# Cosmic_Pi_Main_Board_V2_4_OHWR.net
KiCad netlist of a schematic drawn in EAGLE
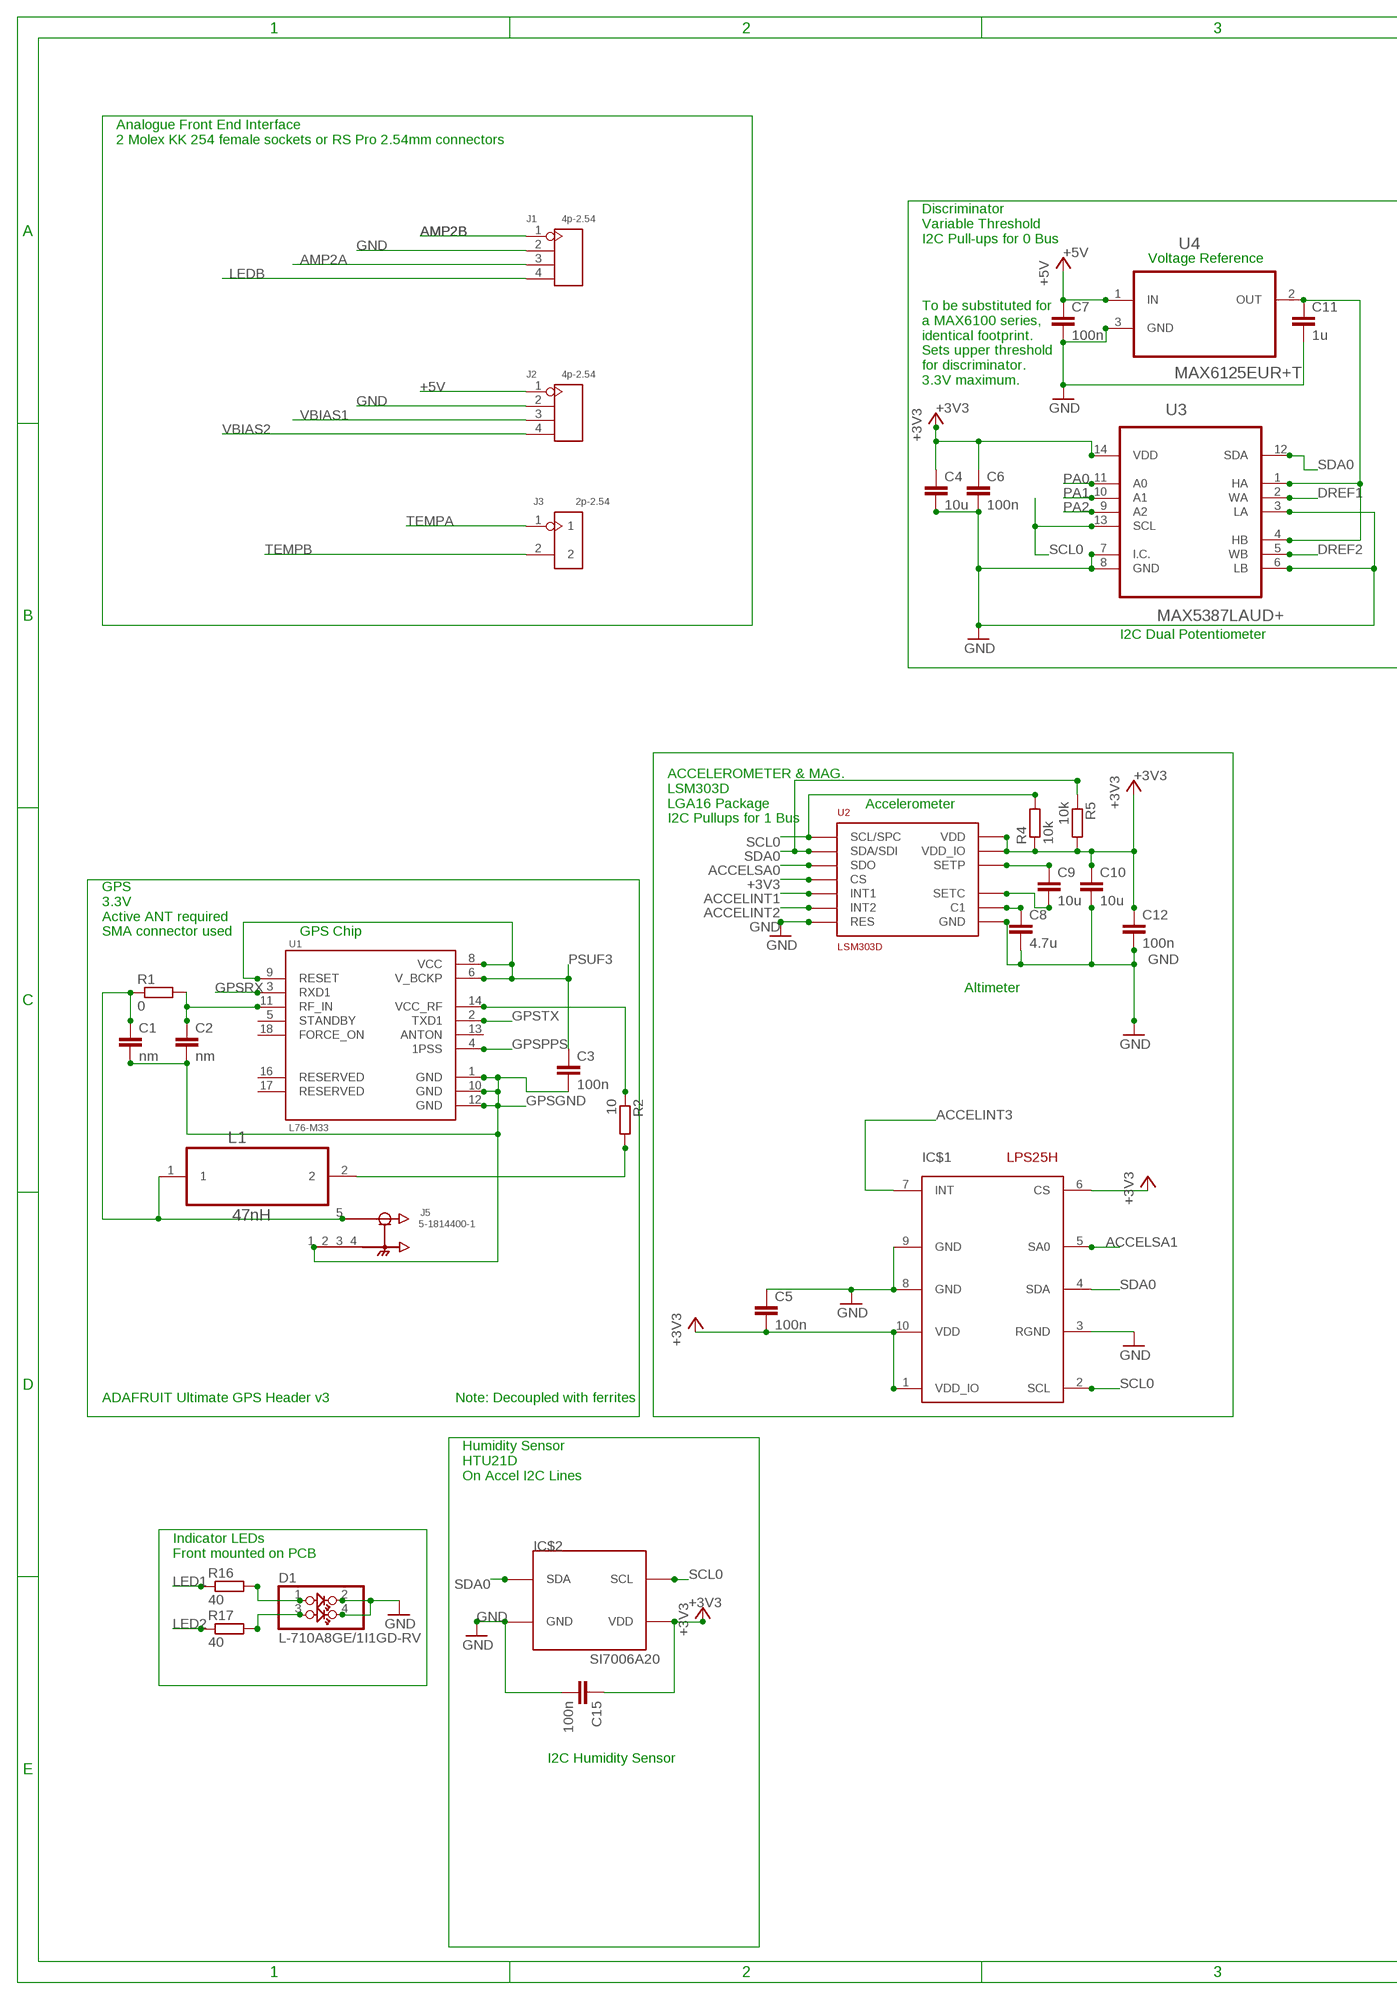
[diagram p0: schematic, sheet 1, part 1 of 2]
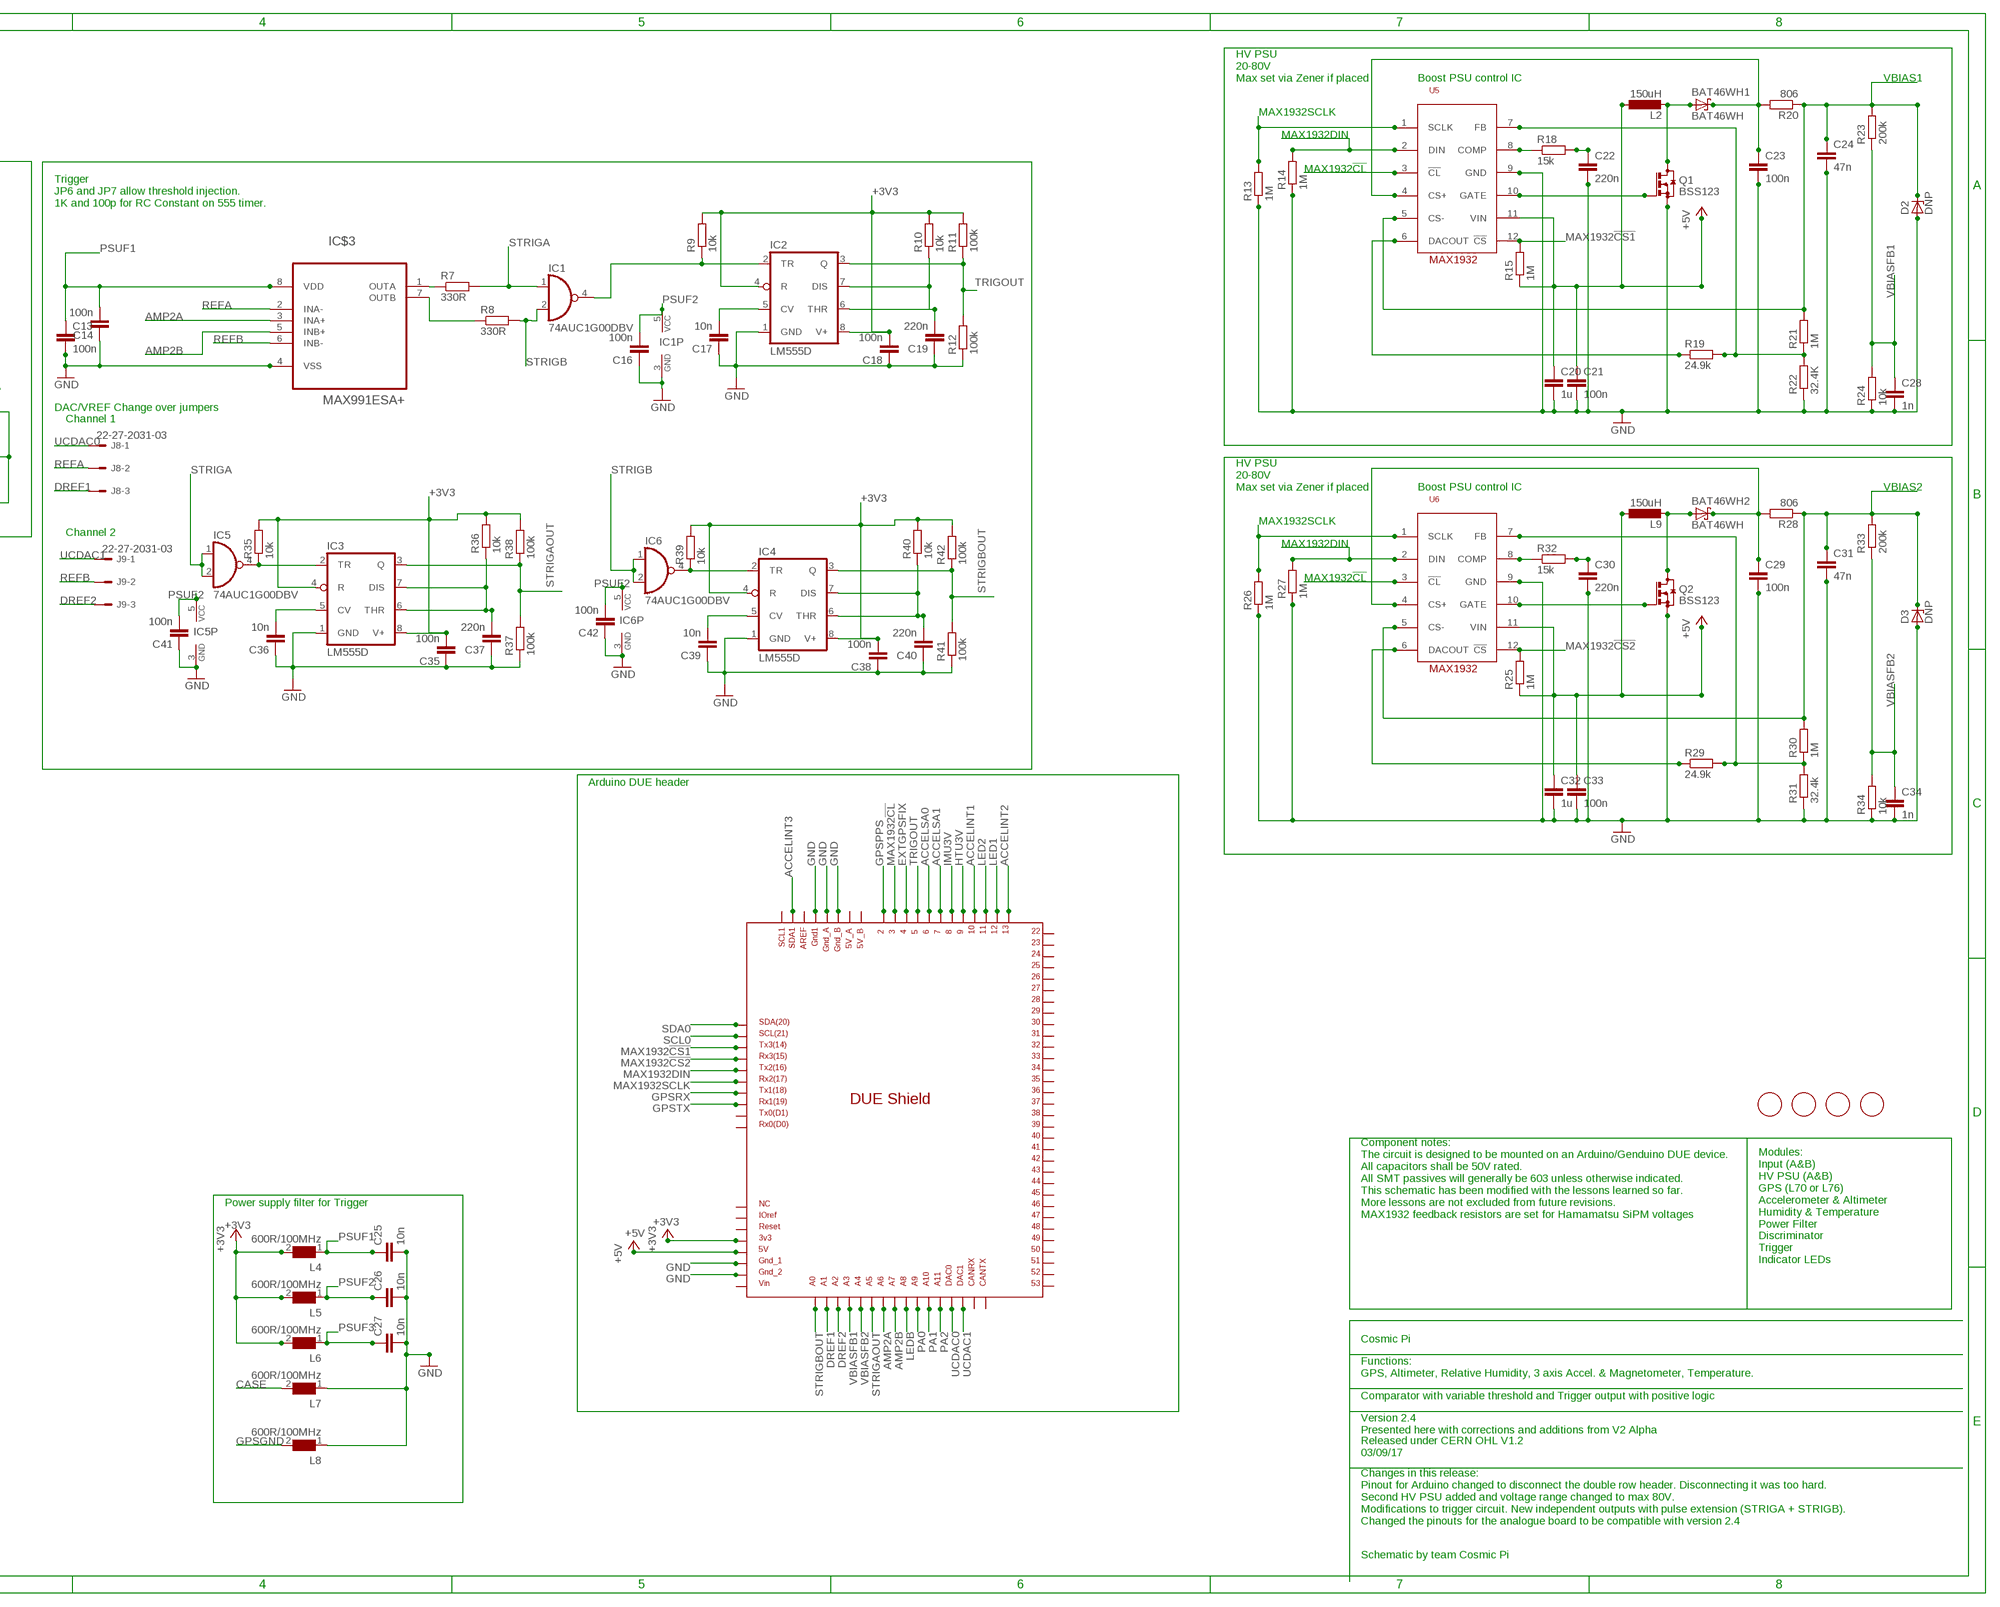
[diagram p1: schematic, sheet 1, part 2 of 2]

(export (version "E")
  (design (tool "Eeschema 10.0.6"))
  (components
    (comp (ref "BAT46WH1")
      (value "BAT46WH")
      (footprint "eagle-import:SOD123F")
      (libsource (lib "eagle-import") (part "BAT46WH"))
    )
    (comp (ref "BAT46WH2")
      (value "BAT46WH")
      (footprint "eagle-import:SOD123F")
      (libsource (lib "eagle-import") (part "BAT46WH"))
    )
    (comp (ref "C1")
      (value "nm")
      (footprint "eagle-import:C0603")
      (libsource (lib "eagle-import") (part "resistor_348_C-EUC0603"))
    )
    (comp (ref "C2")
      (value "nm")
      (footprint "eagle-import:C0603")
      (libsource (lib "eagle-import") (part "resistor_348_C-EUC0603"))
    )
    (comp (ref "C3")
      (value "100n")
      (footprint "eagle-import:C0603")
      (libsource (lib "eagle-import") (part "resistor_348_C-EUC0603"))
    )
    (comp (ref "C4")
      (value "10u")
      (footprint "eagle-import:C0603")
      (libsource (lib "eagle-import") (part "resistor_348_C-EUC0603"))
    )
    (comp (ref "C5")
      (value "100n")
      (footprint "eagle-import:C0603")
      (libsource (lib "eagle-import") (part "resistor_348_C-EUC0603"))
    )
    (comp (ref "C6")
      (value "100n")
      (footprint "eagle-import:C0603")
      (libsource (lib "eagle-import") (part "resistor_348_C-EUC0603"))
    )
    (comp (ref "C7")
      (value "100n")
      (footprint "eagle-import:C0603")
      (libsource (lib "eagle-import") (part "resistor_348_C-EUC0603"))
    )
    (comp (ref "C8")
      (value "4.7u")
      (footprint "eagle-import:C0603")
      (libsource (lib "eagle-import") (part "resistor_348_C-EUC0603"))
    )
    (comp (ref "C9")
      (value "10u")
      (footprint "eagle-import:C0603")
      (libsource (lib "eagle-import") (part "resistor_348_C-EUC0603"))
    )
    (comp (ref "C10")
      (value "10u")
      (footprint "eagle-import:C0603")
      (libsource (lib "eagle-import") (part "resistor_348_C-EUC0603"))
    )
    (comp (ref "C11")
      (value "1u")
      (footprint "eagle-import:C0603")
      (libsource (lib "eagle-import") (part "resistor_348_C-EUC0603"))
    )
    (comp (ref "C12")
      (value "100n")
      (footprint "eagle-import:C0603")
      (libsource (lib "eagle-import") (part "resistor_348_C-EUC0603"))
    )
    (comp (ref "C13")
      (value "100n")
      (footprint "eagle-import:C0603")
      (libsource (lib "eagle-import") (part "resistor_348_C-EUC0603"))
    )
    (comp (ref "C14")
      (value "100n")
      (footprint "eagle-import:C0603")
      (libsource (lib "eagle-import") (part "resistor_348_C-EUC0603"))
    )
    (comp (ref "C15")
      (value "100n")
      (footprint "eagle-import:C0603")
      (libsource (lib "eagle-import") (part "resistor_348_C-EUC0603"))
    )
    (comp (ref "C16")
      (value "100n")
      (footprint "eagle-import:C0603")
      (libsource (lib "eagle-import") (part "resistor_348_C-EUC0603"))
    )
    (comp (ref "C17")
      (value "10n")
      (footprint "eagle-import:C0603")
      (libsource (lib "eagle-import") (part "resistor_348_C-EUC0603"))
    )
    (comp (ref "C18")
      (value "100n")
      (footprint "eagle-import:C0603")
      (libsource (lib "eagle-import") (part "resistor_348_C-EUC0603"))
    )
    (comp (ref "C19")
      (value "220n")
      (footprint "eagle-import:C0603")
      (libsource (lib "eagle-import") (part "resistor_348_C-EUC0603"))
    )
    (comp (ref "C20")
      (value "1u")
      (footprint "eagle-import:C0603")
      (libsource (lib "eagle-import") (part "resistor_348_C-EUC0603"))
    )
    (comp (ref "C21")
      (value "100n")
      (footprint "eagle-import:C0603")
      (libsource (lib "eagle-import") (part "resistor_348_C-EUC0603"))
    )
    (comp (ref "C22")
      (value "220n")
      (footprint "eagle-import:C0603")
      (libsource (lib "eagle-import") (part "C-EUC0603"))
    )
    (comp (ref "C23")
      (value "100n")
      (footprint "eagle-import:C0603")
      (libsource (lib "eagle-import") (part "C-EUC0603"))
    )
    (comp (ref "C24")
      (value "47n")
      (footprint "eagle-import:C0603")
      (libsource (lib "eagle-import") (part "C-EUC0603"))
    )
    (comp (ref "C25")
      (value "10n")
      (footprint "eagle-import:C0603")
      (libsource (lib "eagle-import") (part "resistor_348_C-EUC0603"))
    )
    (comp (ref "C26")
      (value "10n")
      (footprint "eagle-import:C0603")
      (libsource (lib "eagle-import") (part "resistor_348_C-EUC0603"))
    )
    (comp (ref "C27")
      (value "10n")
      (footprint "eagle-import:C0603")
      (libsource (lib "eagle-import") (part "resistor_348_C-EUC0603"))
    )
    (comp (ref "C28")
      (value "1n")
      (footprint "eagle-import:C0603")
      (libsource (lib "eagle-import") (part "C-EUC0603"))
    )
    (comp (ref "C29")
      (value "100n")
      (footprint "eagle-import:C0603")
      (libsource (lib "eagle-import") (part "C-EUC0603"))
    )
    (comp (ref "C30")
      (value "220n")
      (footprint "eagle-import:C0603")
      (libsource (lib "eagle-import") (part "C-EUC0603"))
    )
    (comp (ref "C31")
      (value "47n")
      (footprint "eagle-import:C0603")
      (libsource (lib "eagle-import") (part "C-EUC0603"))
    )
    (comp (ref "C32")
      (value "1u")
      (footprint "eagle-import:C0603")
      (libsource (lib "eagle-import") (part "resistor_348_C-EUC0603"))
    )
    (comp (ref "C33")
      (value "100n")
      (footprint "eagle-import:C0603")
      (libsource (lib "eagle-import") (part "resistor_348_C-EUC0603"))
    )
    (comp (ref "C34")
      (value "1n")
      (footprint "eagle-import:C0603")
      (libsource (lib "eagle-import") (part "C-EUC0603"))
    )
    (comp (ref "C35")
      (value "100n")
      (footprint "eagle-import:C0603")
      (libsource (lib "eagle-import") (part "resistor_348_C-EUC0603"))
    )
    (comp (ref "C36")
      (value "10n")
      (footprint "eagle-import:C0603")
      (libsource (lib "eagle-import") (part "resistor_348_C-EUC0603"))
    )
    (comp (ref "C37")
      (value "220n")
      (footprint "eagle-import:C0603")
      (libsource (lib "eagle-import") (part "resistor_348_C-EUC0603"))
    )
    (comp (ref "C38")
      (value "100n")
      (footprint "eagle-import:C0603")
      (libsource (lib "eagle-import") (part "resistor_348_C-EUC0603"))
    )
    (comp (ref "C39")
      (value "10n")
      (footprint "eagle-import:C0603")
      (libsource (lib "eagle-import") (part "resistor_348_C-EUC0603"))
    )
    (comp (ref "C40")
      (value "220n")
      (footprint "eagle-import:C0603")
      (libsource (lib "eagle-import") (part "resistor_348_C-EUC0603"))
    )
    (comp (ref "C41")
      (value "100n")
      (footprint "eagle-import:C0603")
      (libsource (lib "eagle-import") (part "resistor_348_C-EUC0603"))
    )
    (comp (ref "C42")
      (value "100n")
      (footprint "eagle-import:C0603")
      (libsource (lib "eagle-import") (part "resistor_348_C-EUC0603"))
    )
    (comp (ref "D1")
      (value "L-710A8GE/1I1GD-RV")
      (footprint "eagle-import:2X02")
      (libsource (lib "eagle-import") (part "KINGBRITET1"))
    )
    (comp (ref "D2")
      (value "DNP")
      (footprint "eagle-import:SOT23")
      (libsource (lib "eagle-import") (part "ZENER-DIODESOT23"))
    )
    (comp (ref "D3")
      (value "DNP")
      (footprint "eagle-import:SOT23")
      (libsource (lib "eagle-import") (part "ZENER-DIODESOT23"))
    )
    (comp (ref "DUE1")
      (value "DUE(NORMAL)")
      (footprint "eagle-import:DUE(NORMAL)")
      (libsource (lib "eagle-import") (part "DUE(NORMAL)"))
    )
    (comp (ref "IC$1")
      (value "LPS25H")
      (footprint "eagle-import:LPS25H")
      (libsource (lib "eagle-import") (part "LPS25H"))
    )
    (comp (ref "IC$2")
      (value "SI7006A20")
      (footprint "eagle-import:3X3DFN")
      (libsource (lib "eagle-import") (part "SI7006A20"))
    )
    (comp (ref "IC$3")
      (value "MAX991ESA+")
      (footprint "eagle-import:SOIC-8")
      (libsource (lib "eagle-import") (part "MAX991ESA+"))
    )
    (comp (ref "IC1")
      (value "74AUC1G00DBV")
      (footprint "eagle-import:SOT23-5")
      (libsource (lib "eagle-import") (part "741G00DBVAUC"))
    )
    (comp (ref "IC2")
      (value "LM555D")
      (footprint "eagle-import:SO08")
      (libsource (lib "eagle-import") (part "555DLM"))
    )
    (comp (ref "IC3")
      (value "LM555D")
      (footprint "eagle-import:SO08")
      (libsource (lib "eagle-import") (part "555DLM"))
    )
    (comp (ref "IC4")
      (value "LM555D")
      (footprint "eagle-import:SO08")
      (libsource (lib "eagle-import") (part "555DLM"))
    )
    (comp (ref "IC5")
      (value "74AUC1G00DBV")
      (footprint "eagle-import:SOT23-5")
      (libsource (lib "eagle-import") (part "741G00DBVAUC"))
    )
    (comp (ref "IC6")
      (value "74AUC1G00DBV")
      (footprint "eagle-import:SOT23-5")
      (libsource (lib "eagle-import") (part "741G00DBVAUC"))
    )
    (comp (ref "J1")
      (value "4p-2.54")
      (footprint "eagle-import:H4-2.54")
      (fields (field (name "MPN") "F185-1104A1BSYA1"))
      (libsource (lib "eagle-import") (part "DIP-BLACK-FEMALE-HEADER-VERT(4P-2.54)"))
    )
    (comp (ref "J2")
      (value "4p-2.54")
      (footprint "eagle-import:H4-2.54")
      (fields (field (name "MPN") "F185-1104A1BSYA1"))
      (libsource (lib "eagle-import") (part "DIP-BLACK-FEMALE-HEADER-VERT(4P-2.54)"))
    )
    (comp (ref "J3")
      (value "2p-2.54")
      (footprint "eagle-import:H2-2.54")
      (fields (field (name "MPN") "P125-1102A0BS116A1"))
      (libsource (lib "eagle-import") (part "DIP-BLACK-MALE-HEADER-VERT(2P-2.54)"))
    )
    (comp (ref "J5")
      (value "5-1814400-1")
      (footprint "eagle-import:TE_5-1814400-1")
      (libsource (lib "eagle-import") (part "5-1814400-1"))
    )
    (comp (ref "J8")
      (value "22-27-2031-03")
      (footprint "eagle-import:6410-03")
      (libsource (lib "eagle-import") (part "22-?-0327-2031"))
    )
    (comp (ref "J9")
      (value "22-27-2031-03")
      (footprint "eagle-import:6410-03")
      (libsource (lib "eagle-import") (part "22-?-0327-2031"))
    )
    (comp (ref "L1")
      (value "47nH")
      (footprint "eagle-import:INDC1608X90N")
      (libsource (lib "eagle-import") (part "B82496C3470J"))
    )
    (comp (ref "L2")
      (value "150uH")
      (footprint "eagle-import:L1812")
      (libsource (lib "eagle-import") (part "L-EUL1812"))
    )
    (comp (ref "L4")
      (value "600R/100MHz")
      (footprint "eagle-import:1206")
      (fields (field (name "MPN") "74279218"))
      (libsource (lib "eagle-import") (part "WE-CBF_1206-74279218"))
    )
    (comp (ref "L5")
      (value "600R/100MHz")
      (footprint "eagle-import:1206")
      (fields (field (name "MPN") "74279218"))
      (libsource (lib "eagle-import") (part "WE-CBF_1206-74279218"))
    )
    (comp (ref "L6")
      (value "600R/100MHz")
      (footprint "eagle-import:1206")
      (fields (field (name "MPN") "74279218"))
      (libsource (lib "eagle-import") (part "WE-CBF_1206-74279218"))
    )
    (comp (ref "L7")
      (value "600R/100MHz")
      (footprint "eagle-import:1206")
      (fields (field (name "MPN") "74279218"))
      (libsource (lib "eagle-import") (part "WE-CBF_1206-74279218"))
    )
    (comp (ref "L8")
      (value "600R/100MHz")
      (footprint "eagle-import:1206")
      (fields (field (name "MPN") "74279218"))
      (libsource (lib "eagle-import") (part "WE-CBF_1206-74279218"))
    )
    (comp (ref "L9")
      (value "150uH")
      (footprint "eagle-import:L1812")
      (libsource (lib "eagle-import") (part "L-EUL1812"))
    )
    (comp (ref "Q1")
      (value "BSS123")
      (footprint "eagle-import:SOT23")
      (libsource (lib "eagle-import") (part "BSS123"))
    )
    (comp (ref "Q2")
      (value "BSS123")
      (footprint "eagle-import:SOT23")
      (libsource (lib "eagle-import") (part "BSS123"))
    )
    (comp (ref "R1")
      (value "0")
      (footprint "eagle-import:R0603")
      (libsource (lib "eagle-import") (part "R-EU_R0603"))
    )
    (comp (ref "R2")
      (value "10")
      (footprint "eagle-import:R0603")
      (libsource (lib "eagle-import") (part "R-EU_R0603"))
    )
    (comp (ref "R4")
      (value "10k")
      (footprint "eagle-import:R0603")
      (libsource (lib "eagle-import") (part "R-EU_R0603"))
    )
    (comp (ref "R5")
      (value "10k")
      (footprint "eagle-import:R0603")
      (libsource (lib "eagle-import") (part "R-EU_R0603"))
    )
    (comp (ref "R7")
      (value "330R")
      (footprint "eagle-import:R0603")
      (libsource (lib "eagle-import") (part "R-EU_R0603"))
    )
    (comp (ref "R8")
      (value "330R")
      (footprint "eagle-import:R0603")
      (libsource (lib "eagle-import") (part "R-EU_R0603"))
    )
    (comp (ref "R9")
      (value "10k")
      (footprint "eagle-import:R0603")
      (libsource (lib "eagle-import") (part "R-EU_R0603"))
    )
    (comp (ref "R10")
      (value "10k")
      (footprint "eagle-import:R0603")
      (libsource (lib "eagle-import") (part "R-EU_R0603"))
    )
    (comp (ref "R11")
      (value "100k")
      (footprint "eagle-import:R0603")
      (libsource (lib "eagle-import") (part "R-EU_R0603"))
    )
    (comp (ref "R12")
      (value "100k")
      (footprint "eagle-import:R0603")
      (libsource (lib "eagle-import") (part "R-EU_R0603"))
    )
    (comp (ref "R13")
      (value "1M")
      (footprint "eagle-import:R0603")
      (libsource (lib "eagle-import") (part "R-EU_R0603"))
    )
    (comp (ref "R14")
      (value "1M")
      (footprint "eagle-import:R0603")
      (libsource (lib "eagle-import") (part "R-EU_R0603"))
    )
    (comp (ref "R15")
      (value "1M")
      (footprint "eagle-import:R0603")
      (libsource (lib "eagle-import") (part "R-EU_R0603"))
    )
    (comp (ref "R16")
      (value "40")
      (footprint "eagle-import:R0603")
      (libsource (lib "eagle-import") (part "R-EU_R0603"))
    )
    (comp (ref "R17")
      (value "40")
      (footprint "eagle-import:R0603")
      (libsource (lib "eagle-import") (part "R-EU_R0603"))
    )
    (comp (ref "R18")
      (value "15k")
      (footprint "eagle-import:R0603")
      (libsource (lib "eagle-import") (part "R-EU_R0603"))
    )
    (comp (ref "R19")
      (value "24.9k")
      (footprint "eagle-import:R0603")
      (libsource (lib "eagle-import") (part "R-EU_R0603"))
    )
    (comp (ref "R20")
      (value "806")
      (footprint "eagle-import:R0603")
      (libsource (lib "eagle-import") (part "R-EU_R0603"))
    )
    (comp (ref "R21")
      (value "1M")
      (footprint "eagle-import:R0603")
      (libsource (lib "eagle-import") (part "R-EU_R0603"))
    )
    (comp (ref "R22")
      (value "32.4K")
      (footprint "eagle-import:R0603")
      (libsource (lib "eagle-import") (part "R-EU_R0603"))
    )
    (comp (ref "R23")
      (value "200k")
      (footprint "eagle-import:R0603")
      (libsource (lib "eagle-import") (part "R-EU_R0603"))
    )
    (comp (ref "R24")
      (value "10k")
      (footprint "eagle-import:R0603")
      (libsource (lib "eagle-import") (part "R-EU_R0603"))
    )
    (comp (ref "R25")
      (value "1M")
      (footprint "eagle-import:R0603")
      (libsource (lib "eagle-import") (part "R-EU_R0603"))
    )
    (comp (ref "R26")
      (value "1M")
      (footprint "eagle-import:R0603")
      (libsource (lib "eagle-import") (part "R-EU_R0603"))
    )
    (comp (ref "R27")
      (value "1M")
      (footprint "eagle-import:R0603")
      (libsource (lib "eagle-import") (part "R-EU_R0603"))
    )
    (comp (ref "R28")
      (value "806")
      (footprint "eagle-import:R0603")
      (libsource (lib "eagle-import") (part "R-EU_R0603"))
    )
    (comp (ref "R29")
      (value "24.9k")
      (footprint "eagle-import:R0603")
      (libsource (lib "eagle-import") (part "R-EU_R0603"))
    )
    (comp (ref "R30")
      (value "1M")
      (footprint "eagle-import:R0603")
      (libsource (lib "eagle-import") (part "R-EU_R0603"))
    )
    (comp (ref "R31")
      (value "32.4k")
      (footprint "eagle-import:R0603")
      (libsource (lib "eagle-import") (part "R-EU_R0603"))
    )
    (comp (ref "R32")
      (value "15k")
      (footprint "eagle-import:R0603")
      (libsource (lib "eagle-import") (part "R-EU_R0603"))
    )
    (comp (ref "R33")
      (value "200k")
      (footprint "eagle-import:R0603")
      (libsource (lib "eagle-import") (part "R-EU_R0603"))
    )
    (comp (ref "R34")
      (value "10k")
      (footprint "eagle-import:R0603")
      (libsource (lib "eagle-import") (part "R-EU_R0603"))
    )
    (comp (ref "R35")
      (value "10k")
      (footprint "eagle-import:R0603")
      (libsource (lib "eagle-import") (part "R-EU_R0603"))
    )
    (comp (ref "R36")
      (value "10k")
      (footprint "eagle-import:R0603")
      (libsource (lib "eagle-import") (part "R-EU_R0603"))
    )
    (comp (ref "R37")
      (value "100k")
      (footprint "eagle-import:R0603")
      (libsource (lib "eagle-import") (part "R-EU_R0603"))
    )
    (comp (ref "R38")
      (value "100k")
      (footprint "eagle-import:R0603")
      (libsource (lib "eagle-import") (part "R-EU_R0603"))
    )
    (comp (ref "R39")
      (value "10k")
      (footprint "eagle-import:R0603")
      (libsource (lib "eagle-import") (part "R-EU_R0603"))
    )
    (comp (ref "R40")
      (value "10k")
      (footprint "eagle-import:R0603")
      (libsource (lib "eagle-import") (part "R-EU_R0603"))
    )
    (comp (ref "R41")
      (value "100k")
      (footprint "eagle-import:R0603")
      (libsource (lib "eagle-import") (part "R-EU_R0603"))
    )
    (comp (ref "R42")
      (value "100k")
      (footprint "eagle-import:R0603")
      (libsource (lib "eagle-import") (part "R-EU_R0603"))
    )
    (comp (ref "U$1")
      (value "FIDUCIAL")
      (footprint "eagle-import:FIDUCIAL_1MM")
      (libsource (lib "eagle-import") (part "FIDUCIAL"))
    )
    (comp (ref "U$2")
      (value "FIDUCIAL")
      (footprint "eagle-import:FIDUCIAL_1MM")
      (libsource (lib "eagle-import") (part "FIDUCIAL"))
    )
    (comp (ref "U$3")
      (value "FIDUCIAL")
      (footprint "eagle-import:FIDUCIAL_1MM")
      (libsource (lib "eagle-import") (part "FIDUCIAL"))
    )
    (comp (ref "U$4")
      (value "FIDUCIAL")
      (footprint "eagle-import:FIDUCIAL_1MM")
      (libsource (lib "eagle-import") (part "FIDUCIAL"))
    )
    (comp (ref "U1")
      (value "L76-M33")
      (footprint "eagle-import:CAPCAV110P970X1010X250-18N")
      (libsource (lib "eagle-import") (part "L76-M33"))
    )
    (comp (ref "U2")
      (value "LSM303D")
      (footprint "eagle-import:LGA16L")
      (libsource (lib "eagle-import") (part "LSM303D"))
    )
    (comp (ref "U3")
      (value "MAX5387LAUD+")
      (footprint "eagle-import:TSSOP-14")
      (libsource (lib "eagle-import") (part "MAX5387LAUD+"))
    )
    (comp (ref "U4")
      (value "MAX6125EUR+T")
      (footprint "eagle-import:SOT95P237X112-3N")
      (libsource (lib "eagle-import") (part "MAX6125EUR+T"))
    )
    (comp (ref "U5")
      (value "MAX1932")
      (footprint "eagle-import:TQFN-12")
      (libsource (lib "eagle-import") (part "MAX1932"))
    )
    (comp (ref "U6")
      (value "MAX1932")
      (footprint "eagle-import:TQFN-12")
      (libsource (lib "eagle-import") (part "MAX1932"))
    )
  )
  (nets
    (net (code "1") (name "+3V3") (class "Default")
      (node (ref "C10") (pin "1") (pinfunction "1_1") (pintype "passive"))
      (node (ref "C12") (pin "1") (pinfunction "1_1") (pintype "passive"))
      (node (ref "C15") (pin "1") (pinfunction "1_1") (pintype "passive"))
      (node (ref "C18") (pin "2") (pinfunction "2_2") (pintype "passive"))
      (node (ref "C35") (pin "2") (pinfunction "2_2") (pintype "passive"))
      (node (ref "C38") (pin "2") (pinfunction "2_2") (pintype "passive"))
      (node (ref "C4") (pin "1") (pinfunction "1_1") (pintype "passive"))
      (node (ref "C5") (pin "2") (pinfunction "2_2") (pintype "passive"))
      (node (ref "C6") (pin "1") (pinfunction "1_1") (pintype "passive"))
      (node (ref "DUE1") (pin "3V3") (pinfunction "3V3_3V3") (pintype "bidirectional"))
      (node (ref "IC$1") (pin "1") (pinfunction "VDD_IO_1") (pintype "power_in"))
      (node (ref "IC$1") (pin "10") (pinfunction "VDD_10") (pintype "power_in"))
      (node (ref "IC$1") (pin "6") (pinfunction "CS_6") (pintype "bidirectional"))
      (node (ref "IC$2") (pin "P$5") (pinfunction "VDD_P$5") (pintype "bidirectional"))
      (node (ref "IC2") (pin "4") (pinfunction "R_4") (pintype "input"))
      (node (ref "IC2") (pin "8") (pinfunction "V+_8") (pintype "power_in"))
      (node (ref "IC3") (pin "4") (pinfunction "R_4") (pintype "input"))
      (node (ref "IC3") (pin "8") (pinfunction "V+_8") (pintype "power_in"))
      (node (ref "IC4") (pin "4") (pinfunction "R_4") (pintype "input"))
      (node (ref "IC4") (pin "8") (pinfunction "V+_8") (pintype "power_in"))
      (node (ref "L4") (pin "2") (pinfunction "2_2") (pintype "passive"))
      (node (ref "L5") (pin "2") (pinfunction "2_2") (pintype "passive"))
      (node (ref "L6") (pin "2") (pinfunction "2_2") (pintype "passive"))
      (node (ref "R10") (pin "2") (pinfunction "2_2") (pintype "passive"))
      (node (ref "R11") (pin "2") (pinfunction "2_2") (pintype "passive"))
      (node (ref "R35") (pin "2") (pinfunction "2_2") (pintype "passive"))
      (node (ref "R36") (pin "2") (pinfunction "2_2") (pintype "passive"))
      (node (ref "R38") (pin "2") (pinfunction "2_2") (pintype "passive"))
      (node (ref "R39") (pin "2") (pinfunction "2_2") (pintype "passive"))
      (node (ref "R4") (pin "1") (pinfunction "1_1") (pintype "passive"))
      (node (ref "R40") (pin "2") (pinfunction "2_2") (pintype "passive"))
      (node (ref "R42") (pin "2") (pinfunction "2_2") (pintype "passive"))
      (node (ref "R5") (pin "2") (pinfunction "2_2") (pintype "passive"))
      (node (ref "R9") (pin "2") (pinfunction "2_2") (pintype "passive"))
      (node (ref "U2") (pin "P$1") (pinfunction "VDD_IO_P$1") (pintype "power_in"))
      (node (ref "U2") (pin "P$14") (pinfunction "VDD_P$14") (pintype "power_in"))
      (node (ref "U2") (pin "P$8") (pinfunction "CS_P$8") (pintype "bidirectional"))
      (node (ref "U3") (pin "14") (pinfunction "VDD_14") (pintype "power_in"))
    )
    (net (code "2") (name "+5V") (class "Default")
      (node (ref "C20") (pin "1") (pinfunction "1_1") (pintype "passive"))
      (node (ref "C21") (pin "1") (pinfunction "1_1") (pintype "passive"))
      (node (ref "C32") (pin "1") (pinfunction "1_1") (pintype "passive"))
      (node (ref "C33") (pin "1") (pinfunction "1_1") (pintype "passive"))
      (node (ref "C7") (pin "1") (pinfunction "1_1") (pintype "passive"))
      (node (ref "DUE1") (pin "5V") (pinfunction "5V_5V") (pintype "bidirectional"))
      (node (ref "J2") (pin "1") (pinfunction "P$1_1") (pintype "bidirectional"))
      (node (ref "L2") (pin "1") (pinfunction "1_1") (pintype "passive"))
      (node (ref "L9") (pin "1") (pinfunction "1_1") (pintype "passive"))
      (node (ref "R15") (pin "1") (pinfunction "1_1") (pintype "passive"))
      (node (ref "R25") (pin "1") (pinfunction "1_1") (pintype "passive"))
      (node (ref "U4") (pin "1") (pinfunction "IN_1") (pintype "input"))
      (node (ref "U5") (pin "11") (pinfunction "VIN_11") (pintype "bidirectional"))
      (node (ref "U6") (pin "11") (pinfunction "VIN_11") (pintype "bidirectional"))
    )
    (net (code "3") (name "/ACCELINT1") (class "Default")
      (node (ref "DUE1") (pin "10") (pinfunction "10_10") (pintype "bidirectional"))
      (node (ref "U2") (pin "P$11") (pinfunction "INT1_P$11") (pintype "bidirectional"))
    )
    (net (code "4") (name "/ACCELINT2") (class "Default")
      (node (ref "DUE1") (pin "13") (pinfunction "13_13") (pintype "bidirectional"))
      (node (ref "U2") (pin "P$9") (pinfunction "INT2_P$9") (pintype "bidirectional"))
    )
    (net (code "5") (name "/ACCELINT3") (class "Default")
      (node (ref "DUE1") (pin "SDA1") (pinfunction "SDA1_SDA1") (pintype "bidirectional"))
      (node (ref "IC$1") (pin "7") (pinfunction "INT_7") (pintype "bidirectional"))
    )
    (net (code "6") (name "/ACCELSA0") (class "Default")
      (node (ref "DUE1") (pin "6") (pinfunction "6_6") (pintype "bidirectional"))
      (node (ref "U2") (pin "P$7") (pinfunction "SDO_P$7") (pintype "bidirectional"))
    )
    (net (code "7") (name "/ACCELSA1") (class "Default")
      (node (ref "DUE1") (pin "7") (pinfunction "7_7") (pintype "bidirectional"))
      (node (ref "IC$1") (pin "5") (pinfunction "SA0_5") (pintype "bidirectional"))
    )
    (net (code "8") (name "/AMP2A") (class "Default")
      (node (ref "DUE1") (pin "A6") (pinfunction "A6_A6") (pintype "bidirectional"))
      (node (ref "IC$3") (pin "3") (pinfunction "INA+_3") (pintype "input"))
      (node (ref "J1") (pin "3") (pinfunction "P$3_3") (pintype "bidirectional"))
    )
    (net (code "9") (name "/AMP2B") (class "Default")
      (node (ref "DUE1") (pin "A7") (pinfunction "A7_A7") (pintype "bidirectional"))
      (node (ref "IC$3") (pin "5") (pinfunction "INB+_5") (pintype "input"))
      (node (ref "J1") (pin "1") (pinfunction "P$1_1") (pintype "bidirectional"))
    )
    (net (code "10") (name "/CASE") (class "Default")
      (node (ref "L7") (pin "2") (pinfunction "2_2") (pintype "passive"))
    )
    (net (code "11") (name "/DREF1") (class "Default")
      (node (ref "DUE1") (pin "A1") (pinfunction "A1_A1") (pintype "bidirectional"))
      (node (ref "J8") (pin "3") (pinfunction "S_3") (pintype "passive"))
      (node (ref "U3") (pin "2") (pinfunction "WA_2") (pintype "passive"))
    )
    (net (code "12") (name "/DREF2") (class "Default")
      (node (ref "DUE1") (pin "A2") (pinfunction "A2_A2") (pintype "bidirectional"))
      (node (ref "J9") (pin "3") (pinfunction "S_3") (pintype "passive"))
      (node (ref "U3") (pin "5") (pinfunction "WB_5") (pintype "passive"))
    )
    (net (code "13") (name "/EXTGPSFIX") (class "Default")
      (node (ref "DUE1") (pin "4") (pinfunction "4_4") (pintype "bidirectional"))
    )
    (net (code "14") (name "/GPSGND") (class "Default")
      (node (ref "C1") (pin "2") (pinfunction "2_2") (pintype "passive"))
      (node (ref "C2") (pin "2") (pinfunction "2_2") (pintype "passive"))
      (node (ref "C3") (pin "2") (pinfunction "2_2") (pintype "passive"))
      (node (ref "J5") (pin "1") (pinfunction "GND_1") (pintype "passive"))
      (node (ref "L8") (pin "2") (pinfunction "2_2") (pintype "passive"))
      (node (ref "U1") (pin "1") (pinfunction "GND_1") (pintype "power_in"))
      (node (ref "U1") (pin "10") (pinfunction "GND_10") (pintype "power_in"))
      (node (ref "U1") (pin "12") (pinfunction "GND_12") (pintype "power_in"))
    )
    (net (code "15") (name "/GPSPPS") (class "Default")
      (node (ref "DUE1") (pin "2") (pinfunction "2_2") (pintype "bidirectional"))
      (node (ref "U1") (pin "4") (pinfunction "1PSS_4") (pintype "output"))
    )
    (net (code "16") (name "/GPSRX") (class "Default")
      (node (ref "DUE1") (pin "TX1") (pinfunction "TX1_TX1") (pintype "bidirectional"))
      (node (ref "U1") (pin "3") (pinfunction "RXD1_3") (pintype "bidirectional"))
    )
    (net (code "17") (name "/GPSTX") (class "Default")
      (node (ref "DUE1") (pin "RX1") (pinfunction "RX1_RX1") (pintype "bidirectional"))
      (node (ref "U1") (pin "2") (pinfunction "TXD1_2") (pintype "output"))
    )
    (net (code "18") (name "/HTU3V") (class "Default")
      (node (ref "DUE1") (pin "9") (pinfunction "9_9") (pintype "bidirectional"))
    )
    (net (code "19") (name "/IMU3V") (class "Default")
      (node (ref "DUE1") (pin "8") (pinfunction "8_8") (pintype "bidirectional"))
    )
    (net (code "20") (name "/LED1") (class "Default")
      (node (ref "DUE1") (pin "12") (pinfunction "12_12") (pintype "bidirectional"))
      (node (ref "R16") (pin "1") (pinfunction "1_1") (pintype "passive"))
    )
    (net (code "21") (name "/LED2") (class "Default")
      (node (ref "DUE1") (pin "11") (pinfunction "11_11") (pintype "bidirectional"))
      (node (ref "R17") (pin "1") (pinfunction "1_1") (pintype "passive"))
    )
    (net (code "22") (name "/LEDB") (class "Default")
      (node (ref "DUE1") (pin "A8") (pinfunction "A8_A8") (pintype "bidirectional"))
      (node (ref "J1") (pin "4") (pinfunction "P$4_4") (pintype "bidirectional"))
    )
    (net (code "23") (name "/MAX1932DIN") (class "Default")
      (node (ref "DUE1") (pin "TX2") (pinfunction "TX2_TX2") (pintype "bidirectional"))
      (node (ref "R14") (pin "2") (pinfunction "2_2") (pintype "passive"))
      (node (ref "R27") (pin "2") (pinfunction "2_2") (pintype "passive"))
      (node (ref "U5") (pin "2") (pinfunction "DIN_2") (pintype "bidirectional"))
      (node (ref "U6") (pin "2") (pinfunction "DIN_2") (pintype "bidirectional"))
    )
    (net (code "24") (name "/MAX1932SCLK") (class "Default")
      (node (ref "DUE1") (pin "RX2") (pinfunction "RX2_RX2") (pintype "bidirectional"))
      (node (ref "R13") (pin "2") (pinfunction "2_2") (pintype "passive"))
      (node (ref "R26") (pin "2") (pinfunction "2_2") (pintype "passive"))
      (node (ref "U5") (pin "1") (pinfunction "SCLK_1") (pintype "bidirectional"))
      (node (ref "U6") (pin "1") (pinfunction "SCLK_1") (pintype "bidirectional"))
    )
    (net (code "25") (name "/MAX1932~{CL}") (class "Default")
      (node (ref "DUE1") (pin "3") (pinfunction "3_3") (pintype "bidirectional"))
      (node (ref "U5") (pin "3") (pinfunction "~{CL}_3") (pintype "bidirectional"))
      (node (ref "U6") (pin "3") (pinfunction "~{CL}_3") (pintype "bidirectional"))
    )
    (net (code "26") (name "/MAX1932~{CS1}") (class "Default")
      (node (ref "DUE1") (pin "TX3") (pinfunction "TX3_TX3") (pintype "bidirectional"))
      (node (ref "R15") (pin "2") (pinfunction "2_2") (pintype "passive"))
      (node (ref "U5") (pin "12") (pinfunction "~{CS}_12") (pintype "bidirectional"))
    )
    (net (code "27") (name "/MAX1932~{CS2}") (class "Default")
      (node (ref "DUE1") (pin "RX3") (pinfunction "RX3_RX3") (pintype "bidirectional"))
      (node (ref "R25") (pin "2") (pinfunction "2_2") (pintype "passive"))
      (node (ref "U6") (pin "12") (pinfunction "~{CS}_12") (pintype "bidirectional"))
    )
    (net (code "28") (name "/PA0") (class "Default")
      (node (ref "DUE1") (pin "A9") (pinfunction "A9_A9") (pintype "bidirectional"))
      (node (ref "U3") (pin "11") (pinfunction "A0_11") (pintype "input"))
    )
    (net (code "29") (name "/PA1") (class "Default")
      (node (ref "DUE1") (pin "A10") (pinfunction "A10_A10") (pintype "bidirectional"))
      (node (ref "U3") (pin "10") (pinfunction "A1_10") (pintype "input"))
    )
    (net (code "30") (name "/PA2") (class "Default")
      (node (ref "DUE1") (pin "A11") (pinfunction "A11_A11") (pintype "bidirectional"))
      (node (ref "U3") (pin "9") (pinfunction "A2_9") (pintype "input"))
    )
    (net (code "31") (name "/PSUF1") (class "Default")
      (node (ref "C13") (pin "1") (pinfunction "1_1") (pintype "passive"))
      (node (ref "C14") (pin "2") (pinfunction "2_2") (pintype "passive"))
      (node (ref "C25") (pin "1") (pinfunction "1_1") (pintype "passive"))
      (node (ref "IC$3") (pin "8") (pinfunction "VDD_8") (pintype "power_in"))
      (node (ref "L4") (pin "1") (pinfunction "1_1") (pintype "passive"))
    )
    (net (code "32") (name "/PSUF2") (class "Default")
      (node (ref "C16") (pin "2") (pinfunction "2_2") (pintype "passive"))
      (node (ref "C26") (pin "1") (pinfunction "1_1") (pintype "passive"))
      (node (ref "C41") (pin "2") (pinfunction "2_2") (pintype "passive"))
      (node (ref "C42") (pin "2") (pinfunction "2_2") (pintype "passive"))
      (node (ref "IC1") (pin "5") (pinfunction "VCC_5") (pintype "power_in"))
      (node (ref "IC5") (pin "5") (pinfunction "VCC_5") (pintype "power_in"))
      (node (ref "IC6") (pin "5") (pinfunction "VCC_5") (pintype "power_in"))
      (node (ref "L5") (pin "1") (pinfunction "1_1") (pintype "passive"))
    )
    (net (code "33") (name "/PSUF3") (class "Default")
      (node (ref "C27") (pin "1") (pinfunction "1_1") (pintype "passive"))
      (node (ref "C3") (pin "1") (pinfunction "1_1") (pintype "passive"))
      (node (ref "L6") (pin "1") (pinfunction "1_1") (pintype "passive"))
      (node (ref "U1") (pin "6") (pinfunction "V_BCKP_6") (pintype "power_in"))
      (node (ref "U1") (pin "8") (pinfunction "VCC_8") (pintype "power_in"))
      (node (ref "U1") (pin "9") (pinfunction "RESET_9") (pintype "bidirectional"))
    )
    (net (code "34") (name "/REFA") (class "Default")
      (node (ref "IC$3") (pin "2") (pinfunction "INA-_2") (pintype "input"))
      (node (ref "J8") (pin "2") (pinfunction "S_2") (pintype "passive"))
    )
    (net (code "35") (name "/REFB") (class "Default")
      (node (ref "IC$3") (pin "6") (pinfunction "INB-_6") (pintype "input"))
      (node (ref "J9") (pin "2") (pinfunction "S_2") (pintype "passive"))
    )
    (net (code "36") (name "/SCL0") (class "Default")
      (node (ref "DUE1") (pin "SCL") (pinfunction "SCL_SCL") (pintype "bidirectional"))
      (node (ref "IC$1") (pin "2") (pinfunction "SCL_2") (pintype "bidirectional"))
      (node (ref "IC$2") (pin "P$6") (pinfunction "SCL_P$6") (pintype "bidirectional"))
      (node (ref "R4") (pin "2") (pinfunction "2_2") (pintype "passive"))
      (node (ref "U2") (pin "P$4") (pinfunction "SCL/SPC_P$4") (pintype "bidirectional"))
      (node (ref "U3") (pin "13") (pinfunction "SCL_13") (pintype "input"))
    )
    (net (code "37") (name "/SDA0") (class "Default")
      (node (ref "DUE1") (pin "SDA") (pinfunction "SDA_SDA") (pintype "bidirectional"))
      (node (ref "IC$1") (pin "4") (pinfunction "SDA_4") (pintype "bidirectional"))
      (node (ref "IC$2") (pin "P$1") (pinfunction "SDA_P$1") (pintype "bidirectional"))
      (node (ref "R5") (pin "1") (pinfunction "1_1") (pintype "passive"))
      (node (ref "U2") (pin "P$6") (pinfunction "SDA/SDI_P$6") (pintype "bidirectional"))
      (node (ref "U3") (pin "12") (pinfunction "SDA_12") (pintype "bidirectional"))
    )
    (net (code "38") (name "/STRIGA") (class "Default")
      (node (ref "IC1") (pin "1") (pinfunction "I0_1") (pintype "input"))
      (node (ref "IC5") (pin "1") (pinfunction "I0_1") (pintype "input"))
      (node (ref "IC5") (pin "2") (pinfunction "I1_2") (pintype "input"))
      (node (ref "R7") (pin "2") (pinfunction "2_2") (pintype "passive"))
    )
    (net (code "39") (name "/STRIGAOUT") (class "Default")
      (node (ref "DUE1") (pin "A5") (pinfunction "A5_A5") (pintype "bidirectional"))
      (node (ref "IC3") (pin "3") (pinfunction "Q_3") (pintype "output"))
      (node (ref "R37") (pin "2") (pinfunction "2_2") (pintype "passive"))
      (node (ref "R38") (pin "1") (pinfunction "1_1") (pintype "passive"))
    )
    (net (code "40") (name "/STRIGB") (class "Default")
      (node (ref "IC1") (pin "2") (pinfunction "I1_2") (pintype "input"))
      (node (ref "IC6") (pin "1") (pinfunction "I0_1") (pintype "input"))
      (node (ref "IC6") (pin "2") (pinfunction "I1_2") (pintype "input"))
      (node (ref "R8") (pin "2") (pinfunction "2_2") (pintype "passive"))
    )
    (net (code "41") (name "/STRIGBOUT") (class "Default")
      (node (ref "DUE1") (pin "A0") (pinfunction "A0_A0") (pintype "bidirectional"))
      (node (ref "IC4") (pin "3") (pinfunction "Q_3") (pintype "output"))
      (node (ref "R41") (pin "2") (pinfunction "2_2") (pintype "passive"))
      (node (ref "R42") (pin "1") (pinfunction "1_1") (pintype "passive"))
    )
    (net (code "42") (name "/TEMPA") (class "Default")
      (node (ref "J3") (pin "1") (pinfunction "1_1") (pintype "bidirectional"))
    )
    (net (code "43") (name "/TEMPB") (class "Default")
      (node (ref "J3") (pin "2") (pinfunction "2_2") (pintype "bidirectional"))
    )
    (net (code "44") (name "/TRIGOUT") (class "Default")
      (node (ref "DUE1") (pin "5") (pinfunction "5_5") (pintype "bidirectional"))
      (node (ref "IC2") (pin "3") (pinfunction "Q_3") (pintype "output"))
      (node (ref "R11") (pin "1") (pinfunction "1_1") (pintype "passive"))
      (node (ref "R12") (pin "2") (pinfunction "2_2") (pintype "passive"))
    )
    (net (code "45") (name "/UCDAC0") (class "Default")
      (node (ref "DUE1") (pin "DAC0") (pinfunction "DAC0_DAC0") (pintype "bidirectional"))
      (node (ref "J8") (pin "1") (pinfunction "S_1") (pintype "passive"))
    )
    (net (code "46") (name "/UCDAC1") (class "Default")
      (node (ref "DUE1") (pin "DAC1") (pinfunction "DAC1_DAC1") (pintype "bidirectional"))
      (node (ref "J9") (pin "1") (pinfunction "S_1") (pintype "passive"))
    )
    (net (code "47") (name "/VBIAS1") (class "Default")
      (node (ref "C24") (pin "1") (pinfunction "1_1") (pintype "passive"))
      (node (ref "D2") (pin "3") (pinfunction "C_3") (pintype "passive"))
      (node (ref "J2") (pin "3") (pinfunction "P$3_3") (pintype "bidirectional"))
      (node (ref "R20") (pin "1") (pinfunction "1_1") (pintype "passive"))
      (node (ref "R21") (pin "2") (pinfunction "2_2") (pintype "passive"))
      (node (ref "R23") (pin "2") (pinfunction "2_2") (pintype "passive"))
      (node (ref "U5") (pin "5") (pinfunction "CS-_5") (pintype "bidirectional"))
    )
    (net (code "48") (name "/VBIAS2") (class "Default")
      (node (ref "C31") (pin "1") (pinfunction "1_1") (pintype "passive"))
      (node (ref "D3") (pin "3") (pinfunction "C_3") (pintype "passive"))
      (node (ref "J2") (pin "4") (pinfunction "P$4_4") (pintype "bidirectional"))
      (node (ref "R28") (pin "1") (pinfunction "1_1") (pintype "passive"))
      (node (ref "R30") (pin "2") (pinfunction "2_2") (pintype "passive"))
      (node (ref "R33") (pin "2") (pinfunction "2_2") (pintype "passive"))
      (node (ref "U6") (pin "5") (pinfunction "CS-_5") (pintype "bidirectional"))
    )
    (net (code "49") (name "/VBIASFB1") (class "Default")
      (node (ref "C28") (pin "1") (pinfunction "1_1") (pintype "passive"))
      (node (ref "DUE1") (pin "A3") (pinfunction "A3_A3") (pintype "bidirectional"))
      (node (ref "R23") (pin "1") (pinfunction "1_1") (pintype "passive"))
      (node (ref "R24") (pin "2") (pinfunction "2_2") (pintype "passive"))
    )
    (net (code "50") (name "/VBIASFB2") (class "Default")
      (node (ref "C34") (pin "1") (pinfunction "1_1") (pintype "passive"))
      (node (ref "DUE1") (pin "A4") (pinfunction "A4_A4") (pintype "bidirectional"))
      (node (ref "R33") (pin "1") (pinfunction "1_1") (pintype "passive"))
      (node (ref "R34") (pin "2") (pinfunction "2_2") (pintype "passive"))
    )
    (net (code "51") (name "GND") (class "Default")
      (node (ref "C10") (pin "2") (pinfunction "2_2") (pintype "passive"))
      (node (ref "C11") (pin "2") (pinfunction "2_2") (pintype "passive"))
      (node (ref "C12") (pin "2") (pinfunction "2_2") (pintype "passive"))
      (node (ref "C13") (pin "2") (pinfunction "2_2") (pintype "passive"))
      (node (ref "C14") (pin "1") (pinfunction "1_1") (pintype "passive"))
      (node (ref "C15") (pin "2") (pinfunction "2_2") (pintype "passive"))
      (node (ref "C16") (pin "1") (pinfunction "1_1") (pintype "passive"))
      (node (ref "C17") (pin "1") (pinfunction "1_1") (pintype "passive"))
      (node (ref "C18") (pin "1") (pinfunction "1_1") (pintype "passive"))
      (node (ref "C19") (pin "1") (pinfunction "1_1") (pintype "passive"))
      (node (ref "C20") (pin "2") (pinfunction "2_2") (pintype "passive"))
      (node (ref "C21") (pin "2") (pinfunction "2_2") (pintype "passive"))
      (node (ref "C22") (pin "2") (pinfunction "2_2") (pintype "passive"))
      (node (ref "C23") (pin "2") (pinfunction "2_2") (pintype "passive"))
      (node (ref "C24") (pin "2") (pinfunction "2_2") (pintype "passive"))
      (node (ref "C25") (pin "2") (pinfunction "2_2") (pintype "passive"))
      (node (ref "C26") (pin "2") (pinfunction "2_2") (pintype "passive"))
      (node (ref "C27") (pin "2") (pinfunction "2_2") (pintype "passive"))
      (node (ref "C28") (pin "2") (pinfunction "2_2") (pintype "passive"))
      (node (ref "C29") (pin "2") (pinfunction "2_2") (pintype "passive"))
      (node (ref "C30") (pin "2") (pinfunction "2_2") (pintype "passive"))
      (node (ref "C31") (pin "2") (pinfunction "2_2") (pintype "passive"))
      (node (ref "C32") (pin "2") (pinfunction "2_2") (pintype "passive"))
      (node (ref "C33") (pin "2") (pinfunction "2_2") (pintype "passive"))
      (node (ref "C34") (pin "2") (pinfunction "2_2") (pintype "passive"))
      (node (ref "C35") (pin "1") (pinfunction "1_1") (pintype "passive"))
      (node (ref "C36") (pin "1") (pinfunction "1_1") (pintype "passive"))
      (node (ref "C37") (pin "1") (pinfunction "1_1") (pintype "passive"))
      (node (ref "C38") (pin "1") (pinfunction "1_1") (pintype "passive"))
      (node (ref "C39") (pin "1") (pinfunction "1_1") (pintype "passive"))
      (node (ref "C4") (pin "2") (pinfunction "2_2") (pintype "passive"))
      (node (ref "C40") (pin "1") (pinfunction "1_1") (pintype "passive"))
      (node (ref "C41") (pin "1") (pinfunction "1_1") (pintype "passive"))
      (node (ref "C42") (pin "1") (pinfunction "1_1") (pintype "passive"))
      (node (ref "C5") (pin "1") (pinfunction "1_1") (pintype "passive"))
      (node (ref "C6") (pin "2") (pinfunction "2_2") (pintype "passive"))
      (node (ref "C7") (pin "2") (pinfunction "2_2") (pintype "passive"))
      (node (ref "C8") (pin "2") (pinfunction "2_2") (pintype "passive"))
      (node (ref "D1") (pin "2") (pinfunction "2_2") (pintype "passive"))
      (node (ref "D1") (pin "4") (pinfunction "4_4") (pintype "passive"))
      (node (ref "D2") (pin "1") (pinfunction "A_1") (pintype "passive"))
      (node (ref "D3") (pin "1") (pinfunction "A_1") (pintype "passive"))
      (node (ref "DUE1") (pin "GND1") (pinfunction "GND1_GND1") (pintype "bidirectional"))
      (node (ref "DUE1") (pin "GND_1") (pinfunction "GND_1_GND_1") (pintype "bidirectional"))
      (node (ref "DUE1") (pin "GND_2") (pinfunction "GND_2_GND_2") (pintype "bidirectional"))
      (node (ref "DUE1") (pin "GND_A") (pinfunction "GND_A_GND_A") (pintype "bidirectional"))
      (node (ref "DUE1") (pin "GND_B") (pinfunction "GND_B_GND_B") (pintype "bidirectional"))
      (node (ref "IC$1") (pin "3") (pinfunction "RGND_3") (pintype "bidirectional"))
      (node (ref "IC$1") (pin "8") (pinfunction "GND_8") (pintype "power_in"))
      (node (ref "IC$1") (pin "9") (pinfunction "GND_9") (pintype "power_in"))
      (node (ref "IC$2") (pin "P$2") (pinfunction "GND_P$2") (pintype "bidirectional"))
      (node (ref "IC$3") (pin "4") (pinfunction "VSS_4") (pintype "power_in"))
      (node (ref "IC1") (pin "3") (pinfunction "GND_3") (pintype "power_in"))
      (node (ref "IC2") (pin "1") (pinfunction "GND_1") (pintype "power_in"))
      (node (ref "IC3") (pin "1") (pinfunction "GND_1") (pintype "power_in"))
      (node (ref "IC4") (pin "1") (pinfunction "GND_1") (pintype "power_in"))
      (node (ref "IC5") (pin "3") (pinfunction "GND_3") (pintype "power_in"))
      (node (ref "IC6") (pin "3") (pinfunction "GND_3") (pintype "power_in"))
      (node (ref "J1") (pin "2") (pinfunction "P$2_2") (pintype "bidirectional"))
      (node (ref "J2") (pin "2") (pinfunction "P$2_2") (pintype "bidirectional"))
      (node (ref "L7") (pin "1") (pinfunction "1_1") (pintype "passive"))
      (node (ref "L8") (pin "1") (pinfunction "1_1") (pintype "passive"))
      (node (ref "Q1") (pin "2") (pinfunction "S_2") (pintype "passive"))
      (node (ref "Q2") (pin "2") (pinfunction "S_2") (pintype "passive"))
      (node (ref "R12") (pin "1") (pinfunction "1_1") (pintype "passive"))
      (node (ref "R13") (pin "1") (pinfunction "1_1") (pintype "passive"))
      (node (ref "R14") (pin "1") (pinfunction "1_1") (pintype "passive"))
      (node (ref "R22") (pin "1") (pinfunction "1_1") (pintype "passive"))
      (node (ref "R24") (pin "1") (pinfunction "1_1") (pintype "passive"))
      (node (ref "R26") (pin "1") (pinfunction "1_1") (pintype "passive"))
      (node (ref "R27") (pin "1") (pinfunction "1_1") (pintype "passive"))
      (node (ref "R31") (pin "1") (pinfunction "1_1") (pintype "passive"))
      (node (ref "R34") (pin "1") (pinfunction "1_1") (pintype "passive"))
      (node (ref "R37") (pin "1") (pinfunction "1_1") (pintype "passive"))
      (node (ref "R41") (pin "1") (pinfunction "1_1") (pintype "passive"))
      (node (ref "U2") (pin "P$10") (pinfunction "RES_P$10") (pintype "bidirectional"))
      (node (ref "U2") (pin "P$12") (pinfunction "GND_P$12") (pintype "power_in"))
      (node (ref "U2") (pin "P$13") (pinfunction "GND_P$13") (pintype "power_in"))
      (node (ref "U2") (pin "P$16") (pinfunction "GND_P$16") (pintype "power_in"))
      (node (ref "U2") (pin "P$5") (pinfunction "GND_P$5") (pintype "power_in"))
      (node (ref "U3") (pin "3") (pinfunction "LA_3") (pintype "passive"))
      (node (ref "U3") (pin "6") (pinfunction "LB_6") (pintype "passive"))
      (node (ref "U3") (pin "7") (pinfunction "I.C._7") (pintype "passive"))
      (node (ref "U3") (pin "8") (pinfunction "GND_8") (pintype "passive"))
      (node (ref "U4") (pin "3") (pinfunction "GND_3") (pintype "passive"))
      (node (ref "U5") (pin "9") (pinfunction "GND_9") (pintype "bidirectional"))
      (node (ref "U6") (pin "9") (pinfunction "GND_9") (pintype "bidirectional"))
    )
    (net (code "52") (name "Net-(BAT46WH1-A)") (class "Default")
      (node (ref "BAT46WH1") (pin "2") (pinfunction "A_2") (pintype "passive"))
      (node (ref "L2") (pin "2") (pinfunction "2_2") (pintype "passive"))
      (node (ref "Q1") (pin "3") (pinfunction "D_3") (pintype "passive"))
    )
    (net (code "53") (name "Net-(BAT46WH1-K)") (class "Default")
      (node (ref "BAT46WH1") (pin "1") (pinfunction "K_1") (pintype "passive"))
      (node (ref "C23") (pin "1") (pinfunction "1_1") (pintype "passive"))
      (node (ref "R20") (pin "2") (pinfunction "2_2") (pintype "passive"))
      (node (ref "U5") (pin "4") (pinfunction "CS+_4") (pintype "bidirectional"))
    )
    (net (code "54") (name "Net-(BAT46WH2-A)") (class "Default")
      (node (ref "BAT46WH2") (pin "2") (pinfunction "A_2") (pintype "passive"))
      (node (ref "L9") (pin "2") (pinfunction "2_2") (pintype "passive"))
      (node (ref "Q2") (pin "3") (pinfunction "D_3") (pintype "passive"))
    )
    (net (code "55") (name "Net-(BAT46WH2-K)") (class "Default")
      (node (ref "BAT46WH2") (pin "1") (pinfunction "K_1") (pintype "passive"))
      (node (ref "C29") (pin "1") (pinfunction "1_1") (pintype "passive"))
      (node (ref "R28") (pin "2") (pinfunction "2_2") (pintype "passive"))
      (node (ref "U6") (pin "4") (pinfunction "CS+_4") (pintype "bidirectional"))
    )
    (net (code "56") (name "Net-(C22-Pad1)") (class "Default")
      (node (ref "C22") (pin "1") (pinfunction "1_1") (pintype "passive"))
      (node (ref "R18") (pin "2") (pinfunction "2_2") (pintype "passive"))
    )
    (net (code "57") (name "Net-(C30-Pad1)") (class "Default")
      (node (ref "C30") (pin "1") (pinfunction "1_1") (pintype "passive"))
      (node (ref "R32") (pin "2") (pinfunction "2_2") (pintype "passive"))
    )
    (net (code "58") (name "Net-(D1-Pad1)") (class "Default")
      (node (ref "D1") (pin "1") (pinfunction "1_1") (pintype "passive"))
      (node (ref "R16") (pin "2") (pinfunction "2_2") (pintype "passive"))
    )
    (net (code "59") (name "Net-(D1-Pad3)") (class "Default")
      (node (ref "D1") (pin "3") (pinfunction "3_3") (pintype "passive"))
      (node (ref "R17") (pin "2") (pinfunction "2_2") (pintype "passive"))
    )
    (net (code "60") (name "Net-(IC$3-OUTA)") (class "Default")
      (node (ref "IC$3") (pin "1") (pinfunction "OUTA_1") (pintype "output"))
      (node (ref "R7") (pin "1") (pinfunction "1_1") (pintype "passive"))
    )
    (net (code "61") (name "Net-(IC$3-OUTB)") (class "Default")
      (node (ref "IC$3") (pin "7") (pinfunction "OUTB_7") (pintype "output"))
      (node (ref "R8") (pin "1") (pinfunction "1_1") (pintype "passive"))
    )
    (net (code "62") (name "Net-(IC1A-O)") (class "Default")
      (node (ref "IC1") (pin "4") (pinfunction "O_4") (pintype "output"))
      (node (ref "IC2") (pin "2") (pinfunction "TR_2") (pintype "input"))
      (node (ref "R9") (pin "1") (pinfunction "1_1") (pintype "passive"))
    )
    (net (code "63") (name "Net-(IC2-CV)") (class "Default")
      (node (ref "C17") (pin "2") (pinfunction "2_2") (pintype "passive"))
      (node (ref "IC2") (pin "5") (pinfunction "CV_5") (pintype "input"))
    )
    (net (code "64") (name "Net-(IC2-DIS)") (class "Default")
      (node (ref "C19") (pin "2") (pinfunction "2_2") (pintype "passive"))
      (node (ref "IC2") (pin "6") (pinfunction "THR_6") (pintype "input"))
      (node (ref "IC2") (pin "7") (pinfunction "DIS_7") (pintype "input"))
      (node (ref "R10") (pin "1") (pinfunction "1_1") (pintype "passive"))
    )
    (net (code "65") (name "Net-(IC3-CV)") (class "Default")
      (node (ref "C36") (pin "2") (pinfunction "2_2") (pintype "passive"))
      (node (ref "IC3") (pin "5") (pinfunction "CV_5") (pintype "input"))
    )
    (net (code "66") (name "Net-(IC3-DIS)") (class "Default")
      (node (ref "C37") (pin "2") (pinfunction "2_2") (pintype "passive"))
      (node (ref "IC3") (pin "6") (pinfunction "THR_6") (pintype "input"))
      (node (ref "IC3") (pin "7") (pinfunction "DIS_7") (pintype "input"))
      (node (ref "R36") (pin "1") (pinfunction "1_1") (pintype "passive"))
    )
    (net (code "67") (name "Net-(IC3-TR)") (class "Default")
      (node (ref "IC3") (pin "2") (pinfunction "TR_2") (pintype "input"))
      (node (ref "IC5") (pin "4") (pinfunction "O_4") (pintype "output"))
      (node (ref "R35") (pin "1") (pinfunction "1_1") (pintype "passive"))
    )
    (net (code "68") (name "Net-(IC4-CV)") (class "Default")
      (node (ref "C39") (pin "2") (pinfunction "2_2") (pintype "passive"))
      (node (ref "IC4") (pin "5") (pinfunction "CV_5") (pintype "input"))
    )
    (net (code "69") (name "Net-(IC4-DIS)") (class "Default")
      (node (ref "C40") (pin "2") (pinfunction "2_2") (pintype "passive"))
      (node (ref "IC4") (pin "6") (pinfunction "THR_6") (pintype "input"))
      (node (ref "IC4") (pin "7") (pinfunction "DIS_7") (pintype "input"))
      (node (ref "R40") (pin "1") (pinfunction "1_1") (pintype "passive"))
    )
    (net (code "70") (name "Net-(IC4-TR)") (class "Default")
      (node (ref "IC4") (pin "2") (pinfunction "TR_2") (pintype "input"))
      (node (ref "IC6") (pin "4") (pinfunction "O_4") (pintype "output"))
      (node (ref "R39") (pin "1") (pinfunction "1_1") (pintype "passive"))
    )
    (net (code "71") (name "Net-(J5-SIG)") (class "Default")
      (node (ref "C1") (pin "1") (pinfunction "1_1") (pintype "passive"))
      (node (ref "J5") (pin "5") (pinfunction "SIG_5") (pintype "passive"))
      (node (ref "L1") (pin "1") (pinfunction "1_1") (pintype "passive"))
      (node (ref "R1") (pin "1") (pinfunction "1_1") (pintype "passive"))
    )
    (net (code "72") (name "Net-(L1-Pad2)") (class "Default")
      (node (ref "L1") (pin "2") (pinfunction "2_2") (pintype "passive"))
      (node (ref "R2") (pin "2") (pinfunction "2_2") (pintype "passive"))
    )
    (net (code "73") (name "Net-(Q1-G)") (class "Default")
      (node (ref "Q1") (pin "1") (pinfunction "G_1") (pintype "passive"))
      (node (ref "U5") (pin "10") (pinfunction "GATE_10") (pintype "bidirectional"))
    )
    (net (code "74") (name "Net-(Q2-G)") (class "Default")
      (node (ref "Q2") (pin "1") (pinfunction "G_1") (pintype "passive"))
      (node (ref "U6") (pin "10") (pinfunction "GATE_10") (pintype "bidirectional"))
    )
    (net (code "75") (name "Net-(U1-RF_IN)") (class "Default")
      (node (ref "C2") (pin "1") (pinfunction "1_1") (pintype "passive"))
      (node (ref "R1") (pin "2") (pinfunction "2_2") (pintype "passive"))
      (node (ref "U1") (pin "11") (pinfunction "RF_IN_11") (pintype "bidirectional"))
    )
    (net (code "76") (name "Net-(U1-VCC_RF)") (class "Default")
      (node (ref "R2") (pin "1") (pinfunction "1_1") (pintype "passive"))
      (node (ref "U1") (pin "14") (pinfunction "VCC_RF_14") (pintype "output"))
    )
    (net (code "77") (name "Net-(U2-C1)") (class "Default")
      (node (ref "C8") (pin "1") (pinfunction "1_1") (pintype "passive"))
      (node (ref "U2") (pin "P$15") (pinfunction "C1_P$15") (pintype "bidirectional"))
    )
    (net (code "78") (name "Net-(U2-SETC)") (class "Default")
      (node (ref "C9") (pin "2") (pinfunction "2_2") (pintype "passive"))
      (node (ref "U2") (pin "P$2") (pinfunction "SETC_P$2") (pintype "bidirectional"))
    )
    (net (code "79") (name "Net-(U2-SETP)") (class "Default")
      (node (ref "C9") (pin "1") (pinfunction "1_1") (pintype "passive"))
      (node (ref "U2") (pin "P$3") (pinfunction "SETP_P$3") (pintype "bidirectional"))
    )
    (net (code "80") (name "Net-(U3-HA)") (class "Default")
      (node (ref "C11") (pin "1") (pinfunction "1_1") (pintype "passive"))
      (node (ref "U3") (pin "1") (pinfunction "HA_1") (pintype "passive"))
      (node (ref "U3") (pin "4") (pinfunction "HB_4") (pintype "passive"))
      (node (ref "U4") (pin "2") (pinfunction "OUT_2") (pintype "output"))
    )
    (net (code "81") (name "Net-(U5-COMP)") (class "Default")
      (node (ref "R18") (pin "1") (pinfunction "1_1") (pintype "passive"))
      (node (ref "U5") (pin "8") (pinfunction "COMP_8") (pintype "bidirectional"))
    )
    (net (code "82") (name "Net-(U5-DACOUT)") (class "Default")
      (node (ref "R19") (pin "1") (pinfunction "1_1") (pintype "passive"))
      (node (ref "U5") (pin "6") (pinfunction "DACOUT_6") (pintype "bidirectional"))
    )
    (net (code "83") (name "Net-(U5-FB)") (class "Default")
      (node (ref "R19") (pin "2") (pinfunction "2_2") (pintype "passive"))
      (node (ref "R21") (pin "1") (pinfunction "1_1") (pintype "passive"))
      (node (ref "R22") (pin "2") (pinfunction "2_2") (pintype "passive"))
      (node (ref "U5") (pin "7") (pinfunction "FB_7") (pintype "bidirectional"))
    )
    (net (code "84") (name "Net-(U6-COMP)") (class "Default")
      (node (ref "R32") (pin "1") (pinfunction "1_1") (pintype "passive"))
      (node (ref "U6") (pin "8") (pinfunction "COMP_8") (pintype "bidirectional"))
    )
    (net (code "85") (name "Net-(U6-DACOUT)") (class "Default")
      (node (ref "R29") (pin "1") (pinfunction "1_1") (pintype "passive"))
      (node (ref "U6") (pin "6") (pinfunction "DACOUT_6") (pintype "bidirectional"))
    )
    (net (code "86") (name "Net-(U6-FB)") (class "Default")
      (node (ref "R29") (pin "2") (pinfunction "2_2") (pintype "passive"))
      (node (ref "R30") (pin "1") (pinfunction "1_1") (pintype "passive"))
      (node (ref "R31") (pin "2") (pinfunction "2_2") (pintype "passive"))
      (node (ref "U6") (pin "7") (pinfunction "FB_7") (pintype "bidirectional"))
    )
    (net (code "87") (name "unconnected-(DUE1-Pad5V_A)") (class "Default")
      (node (ref "DUE1") (pin "5V_A") (pinfunction "5V_A_5V_A") (pintype "bidirectional"))
    )
    (net (code "88") (name "unconnected-(DUE1-Pad5V_B)") (class "Default")
      (node (ref "DUE1") (pin "5V_B") (pinfunction "5V_B_5V_B") (pintype "bidirectional"))
    )
    (net (code "89") (name "unconnected-(DUE1-Pad22)") (class "Default")
      (node (ref "DUE1") (pin "22") (pinfunction "22_22") (pintype "bidirectional"))
    )
    (net (code "90") (name "unconnected-(DUE1-Pad23)") (class "Default")
      (node (ref "DUE1") (pin "23") (pinfunction "23_23") (pintype "bidirectional"))
    )
    (net (code "91") (name "unconnected-(DUE1-Pad24)") (class "Default")
      (node (ref "DUE1") (pin "24") (pinfunction "24_24") (pintype "bidirectional"))
    )
    (net (code "92") (name "unconnected-(DUE1-Pad25)") (class "Default")
      (node (ref "DUE1") (pin "25") (pinfunction "25_25") (pintype "bidirectional"))
    )
    (net (code "93") (name "unconnected-(DUE1-Pad26)") (class "Default")
      (node (ref "DUE1") (pin "26") (pinfunction "26_26") (pintype "bidirectional"))
    )
    (net (code "94") (name "unconnected-(DUE1-Pad27)") (class "Default")
      (node (ref "DUE1") (pin "27") (pinfunction "27_27") (pintype "bidirectional"))
    )
    (net (code "95") (name "unconnected-(DUE1-Pad28)") (class "Default")
      (node (ref "DUE1") (pin "28") (pinfunction "28_28") (pintype "bidirectional"))
    )
    (net (code "96") (name "unconnected-(DUE1-Pad29)") (class "Default")
      (node (ref "DUE1") (pin "29") (pinfunction "29_29") (pintype "bidirectional"))
    )
    (net (code "97") (name "unconnected-(DUE1-Pad30)") (class "Default")
      (node (ref "DUE1") (pin "30") (pinfunction "30_30") (pintype "bidirectional"))
    )
    (net (code "98") (name "unconnected-(DUE1-Pad31)") (class "Default")
      (node (ref "DUE1") (pin "31") (pinfunction "31_31") (pintype "bidirectional"))
    )
    (net (code "99") (name "unconnected-(DUE1-Pad32)") (class "Default")
      (node (ref "DUE1") (pin "32") (pinfunction "32_32") (pintype "bidirectional"))
    )
    (net (code "100") (name "unconnected-(DUE1-Pad33)") (class "Default")
      (node (ref "DUE1") (pin "33") (pinfunction "33_33") (pintype "bidirectional"))
    )
    (net (code "101") (name "unconnected-(DUE1-Pad34)") (class "Default")
      (node (ref "DUE1") (pin "34") (pinfunction "34_34") (pintype "bidirectional"))
    )
    (net (code "102") (name "unconnected-(DUE1-Pad35)") (class "Default")
      (node (ref "DUE1") (pin "35") (pinfunction "35_35") (pintype "bidirectional"))
    )
    (net (code "103") (name "unconnected-(DUE1-Pad36)") (class "Default")
      (node (ref "DUE1") (pin "36") (pinfunction "36_36") (pintype "bidirectional"))
    )
    (net (code "104") (name "unconnected-(DUE1-Pad37)") (class "Default")
      (node (ref "DUE1") (pin "37") (pinfunction "37_37") (pintype "bidirectional"))
    )
    (net (code "105") (name "unconnected-(DUE1-Pad38)") (class "Default")
      (node (ref "DUE1") (pin "38") (pinfunction "38_38") (pintype "bidirectional"))
    )
    (net (code "106") (name "unconnected-(DUE1-Pad39)") (class "Default")
      (node (ref "DUE1") (pin "39") (pinfunction "39_39") (pintype "bidirectional"))
    )
    (net (code "107") (name "unconnected-(DUE1-Pad40)") (class "Default")
      (node (ref "DUE1") (pin "40") (pinfunction "40_40") (pintype "bidirectional"))
    )
    (net (code "108") (name "unconnected-(DUE1-Pad41)") (class "Default")
      (node (ref "DUE1") (pin "41") (pinfunction "41_41") (pintype "bidirectional"))
    )
    (net (code "109") (name "unconnected-(DUE1-Pad42)") (class "Default")
      (node (ref "DUE1") (pin "42") (pinfunction "42_42") (pintype "bidirectional"))
    )
    (net (code "110") (name "unconnected-(DUE1-Pad43)") (class "Default")
      (node (ref "DUE1") (pin "43") (pinfunction "43_43") (pintype "bidirectional"))
    )
    (net (code "111") (name "unconnected-(DUE1-Pad44)") (class "Default")
      (node (ref "DUE1") (pin "44") (pinfunction "44_44") (pintype "bidirectional"))
    )
    (net (code "112") (name "unconnected-(DUE1-Pad45)") (class "Default")
      (node (ref "DUE1") (pin "45") (pinfunction "45_45") (pintype "bidirectional"))
    )
    (net (code "113") (name "unconnected-(DUE1-Pad46)") (class "Default")
      (node (ref "DUE1") (pin "46") (pinfunction "46_46") (pintype "bidirectional"))
    )
    (net (code "114") (name "unconnected-(DUE1-Pad47)") (class "Default")
      (node (ref "DUE1") (pin "47") (pinfunction "47_47") (pintype "bidirectional"))
    )
    (net (code "115") (name "unconnected-(DUE1-Pad48)") (class "Default")
      (node (ref "DUE1") (pin "48") (pinfunction "48_48") (pintype "bidirectional"))
    )
    (net (code "116") (name "unconnected-(DUE1-Pad49)") (class "Default")
      (node (ref "DUE1") (pin "49") (pinfunction "49_49") (pintype "bidirectional"))
    )
    (net (code "117") (name "unconnected-(DUE1-Pad50)") (class "Default")
      (node (ref "DUE1") (pin "50") (pinfunction "50_50") (pintype "bidirectional"))
    )
    (net (code "118") (name "unconnected-(DUE1-Pad51)") (class "Default")
      (node (ref "DUE1") (pin "51") (pinfunction "51_51") (pintype "bidirectional"))
    )
    (net (code "119") (name "unconnected-(DUE1-Pad52)") (class "Default")
      (node (ref "DUE1") (pin "52") (pinfunction "52_52") (pintype "bidirectional"))
    )
    (net (code "120") (name "unconnected-(DUE1-Pad53)") (class "Default")
      (node (ref "DUE1") (pin "53") (pinfunction "53_53") (pintype "bidirectional"))
    )
    (net (code "121") (name "unconnected-(DUE1-PadAREF)") (class "Default")
      (node (ref "DUE1") (pin "AREF") (pinfunction "AREF_AREF") (pintype "bidirectional"))
    )
    (net (code "122") (name "unconnected-(DUE1-PadCANRX)") (class "Default")
      (node (ref "DUE1") (pin "CANRX") (pinfunction "CANRX_CANRX") (pintype "bidirectional"))
    )
    (net (code "123") (name "unconnected-(DUE1-PadCANTX)") (class "Default")
      (node (ref "DUE1") (pin "CANTX") (pinfunction "CANTX_CANTX") (pintype "bidirectional"))
    )
    (net (code "124") (name "unconnected-(DUE1-PadIOREF)") (class "Default")
      (node (ref "DUE1") (pin "IOREF") (pinfunction "IOREF_IOREF") (pintype "bidirectional"))
    )
    (net (code "125") (name "unconnected-(DUE1-PadNC)") (class "Default")
      (node (ref "DUE1") (pin "NC") (pinfunction "NC_NC") (pintype "bidirectional"))
    )
    (net (code "126") (name "unconnected-(DUE1-PadRESET)") (class "Default")
      (node (ref "DUE1") (pin "RESET") (pinfunction "RESET_RESET") (pintype "bidirectional"))
    )
    (net (code "127") (name "unconnected-(DUE1-PadRX0)") (class "Default")
      (node (ref "DUE1") (pin "RX0") (pinfunction "RX0_RX0") (pintype "bidirectional"))
    )
    (net (code "128") (name "unconnected-(DUE1-PadSCL1)") (class "Default")
      (node (ref "DUE1") (pin "SCL1") (pinfunction "SCL1_SCL1") (pintype "bidirectional"))
    )
    (net (code "129") (name "unconnected-(DUE1-PadTX0)") (class "Default")
      (node (ref "DUE1") (pin "TX0") (pinfunction "TX0_TX0") (pintype "bidirectional"))
    )
    (net (code "130") (name "unconnected-(DUE1-PadVIN)") (class "Default")
      (node (ref "DUE1") (pin "VIN") (pinfunction "VIN_VIN") (pintype "bidirectional"))
    )
    (net (code "131") (name "unconnected-(J5-GND-Pad2)") (class "Default")
      (node (ref "J5") (pin "2") (pinfunction "GND_2") (pintype "passive"))
    )
    (net (code "132") (name "unconnected-(J5-GND-Pad3)") (class "Default")
      (node (ref "J5") (pin "3") (pinfunction "GND_3") (pintype "passive"))
    )
    (net (code "133") (name "unconnected-(J5-GND-Pad4)") (class "Default")
      (node (ref "J5") (pin "4") (pinfunction "GND_4") (pintype "passive"))
    )
    (net (code "134") (name "unconnected-(U1-ANTON-Pad13)") (class "Default")
      (node (ref "U1") (pin "13") (pinfunction "ANTON_13") (pintype "output"))
    )
    (net (code "135") (name "unconnected-(U1-FORCE_ON-Pad18)") (class "Default")
      (node (ref "U1") (pin "18") (pinfunction "FORCE_ON_18") (pintype "bidirectional"))
    )
    (net (code "136") (name "unconnected-(U1-RESERVED-Pad16)") (class "Default")
      (node (ref "U1") (pin "16") (pinfunction "RESERVED_16") (pintype "passive"))
    )
    (net (code "137") (name "unconnected-(U1-RESERVED-Pad17)") (class "Default")
      (node (ref "U1") (pin "17") (pinfunction "RESERVED_17") (pintype "passive"))
    )
    (net (code "138") (name "unconnected-(U1-STANDBY-Pad5)") (class "Default")
      (node (ref "U1") (pin "5") (pinfunction "STANDBY_5") (pintype "bidirectional"))
    )
  )
)
